# sch.net
KiCad netlist of a schematic drawn in Altium Designer
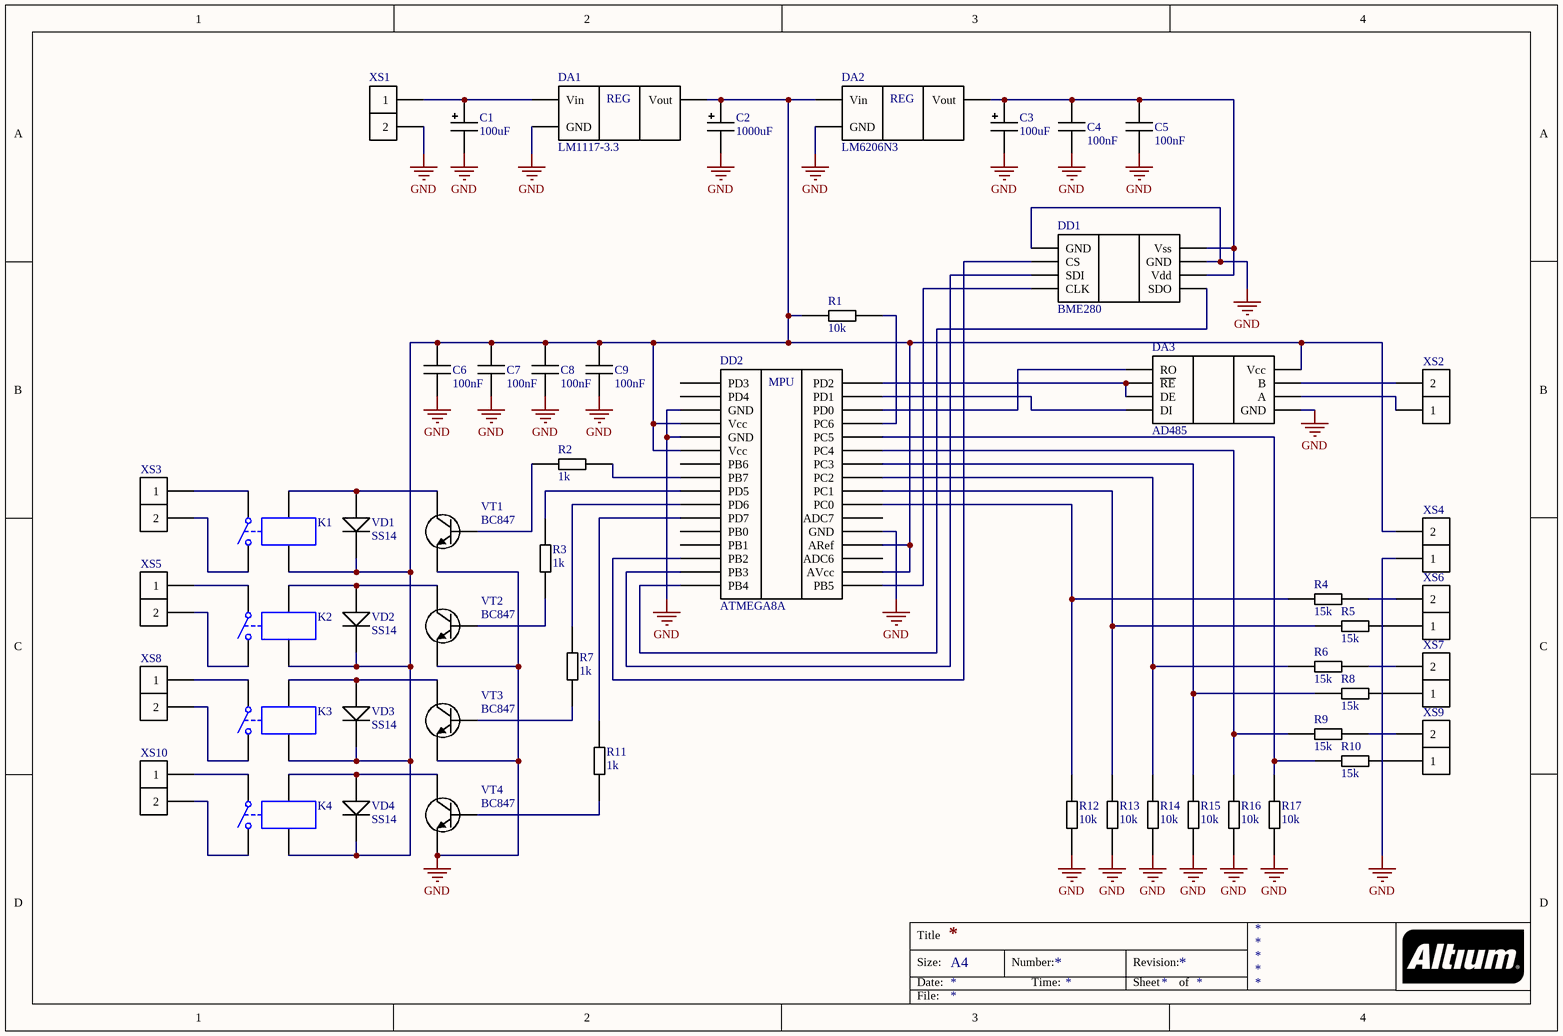
[diagram p0: sch.SchDoc]

(export (version "E")
  (design (tool "Eeschema 10.0.6"))
  (components
    (comp (ref "C1") (value "100uF") (libsource (lib "EDDLib") (part "CAP_POLAR")))
    (comp (ref "C2") (value "1000uF") (libsource (lib "EDDLib") (part "CAP_POLAR")))
    (comp (ref "C3") (value "100uF") (libsource (lib "EDDLib") (part "CAP_POLAR")))
    (comp (ref "C4") (value "100nF") (libsource (lib "EDDLib") (part "CAP_NONPOLAR")))
    (comp (ref "C5") (value "100nF") (libsource (lib "EDDLib") (part "CAP_NONPOLAR")))
    (comp (ref "C6") (value "100nF") (libsource (lib "EDDLib") (part "CAP_NONPOLAR")))
    (comp (ref "C7") (value "100nF") (libsource (lib "EDDLib") (part "CAP_NONPOLAR")))
    (comp (ref "C8") (value "100nF") (libsource (lib "EDDLib") (part "CAP_NONPOLAR")))
    (comp (ref "C9") (value "100nF") (libsource (lib "EDDLib") (part "CAP_NONPOLAR")))
    (comp (ref "DA1") (value "LM1117-3.3") (libsource (lib "EDDLib") (part "LM1117-3.3")))
    (comp (ref "DA2") (value "LM6206N3") (libsource (lib "EDDLib") (part "LM1117-3.3")))
    (comp (ref "DA3") (value "AD485") (libsource (lib "EDDLib") (part "AD485")))
    (comp (ref "DD1") (value "BME280") (libsource (lib "EDDLib") (part "BME280")))
    (comp (ref "DD2") (value "ATMEGA8A") (libsource (lib "EDDLib") (part "ATMEGA8A")))
    (comp (ref "K1")
      (value "Relay-SPST")
      (footprint "MODULE4")
      (description "Single-Pole Single-Throw Relay")
      (fields (field (name "PUBLISHER") "Altium Limited"))
      (libsource (lib "Miscellaneous Devices") (part "Relay-SPST"))
    )
    (comp (ref "K2")
      (value "Relay-SPST")
      (footprint "MODULE4")
      (description "Single-Pole Single-Throw Relay")
      (fields (field (name "PUBLISHER") "Altium Limited"))
      (libsource (lib "Miscellaneous Devices") (part "Relay-SPST"))
    )
    (comp (ref "K3")
      (value "Relay-SPST")
      (footprint "MODULE4")
      (description "Single-Pole Single-Throw Relay")
      (fields (field (name "PUBLISHER") "Altium Limited"))
      (libsource (lib "Miscellaneous Devices") (part "Relay-SPST"))
    )
    (comp (ref "K4")
      (value "Relay-SPST")
      (footprint "MODULE4")
      (description "Single-Pole Single-Throw Relay")
      (fields (field (name "PUBLISHER") "Altium Limited"))
      (libsource (lib "Miscellaneous Devices") (part "Relay-SPST"))
    )
    (comp (ref "R1") (value "10k") (libsource (lib "EDDLib") (part "RES")))
    (comp (ref "R2") (value "1k") (libsource (lib "EDDLib") (part "RES")))
    (comp (ref "R3") (value "1k") (libsource (lib "EDDLib") (part "RES")))
    (comp (ref "R4") (value "15k") (libsource (lib "EDDLib") (part "RES")))
    (comp (ref "R5") (value "15k") (libsource (lib "EDDLib") (part "RES")))
    (comp (ref "R6") (value "15k") (libsource (lib "EDDLib") (part "RES")))
    (comp (ref "R7") (value "1k") (libsource (lib "EDDLib") (part "RES")))
    (comp (ref "R8") (value "15k") (libsource (lib "EDDLib") (part "RES")))
    (comp (ref "R9") (value "15k") (libsource (lib "EDDLib") (part "RES")))
    (comp (ref "R10") (value "15k") (libsource (lib "EDDLib") (part "RES")))
    (comp (ref "R11") (value "1k") (libsource (lib "EDDLib") (part "RES")))
    (comp (ref "R12") (value "10k") (libsource (lib "EDDLib") (part "RES")))
    (comp (ref "R13") (value "10k") (libsource (lib "EDDLib") (part "RES")))
    (comp (ref "R14") (value "10k") (libsource (lib "EDDLib") (part "RES")))
    (comp (ref "R15") (value "10k") (libsource (lib "EDDLib") (part "RES")))
    (comp (ref "R16") (value "10k") (libsource (lib "EDDLib") (part "RES")))
    (comp (ref "R17") (value "10k") (libsource (lib "EDDLib") (part "RES")))
    (comp (ref "VD1")
      (value "SS14")
      (footprint "SMC")
      (description "Default Diode")
      (fields (field (name "PUBLISHER") "Altium Limited"))
      (libsource (lib "EDDLib") (part "Diode"))
    )
    (comp (ref "VD2")
      (value "SS14")
      (footprint "SMC")
      (description "Default Diode")
      (fields (field (name "PUBLISHER") "Altium Limited"))
      (libsource (lib "EDDLib") (part "Diode"))
    )
    (comp (ref "VD3")
      (value "SS14")
      (footprint "SMC")
      (description "Default Diode")
      (fields (field (name "PUBLISHER") "Altium Limited"))
      (libsource (lib "EDDLib") (part "Diode"))
    )
    (comp (ref "VD4")
      (value "SS14")
      (footprint "SMC")
      (description "Default Diode")
      (fields (field (name "PUBLISHER") "Altium Limited"))
      (libsource (lib "EDDLib") (part "Diode"))
    )
    (comp (ref "VT1")
      (value "BC847")
      (footprint "TO-226-AA")
      (description "NPN Bipolar Transistor")
      (fields (field (name "PUBLISHER") "Altium Limited"))
      (libsource (lib "EDDLib") (part "NPN"))
    )
    (comp (ref "VT2")
      (value "BC847")
      (footprint "TO-226-AA")
      (description "NPN Bipolar Transistor")
      (fields (field (name "PUBLISHER") "Altium Limited"))
      (libsource (lib "EDDLib") (part "NPN"))
    )
    (comp (ref "VT3")
      (value "BC847")
      (footprint "TO-226-AA")
      (description "NPN Bipolar Transistor")
      (fields (field (name "PUBLISHER") "Altium Limited"))
      (libsource (lib "EDDLib") (part "NPN"))
    )
    (comp (ref "VT4")
      (value "BC847")
      (footprint "TO-226-AA")
      (description "NPN Bipolar Transistor")
      (fields (field (name "PUBLISHER") "Altium Limited"))
      (libsource (lib "EDDLib") (part "NPN"))
    )
    (comp (ref "XS1") (value "CONN-2") (libsource (lib "EDDLib") (part "CONN-2")))
    (comp (ref "XS2") (value "CONN-2") (libsource (lib "EDDLib") (part "CONN-2")))
    (comp (ref "XS3") (value "CONN-2") (libsource (lib "EDDLib") (part "CONN-2")))
    (comp (ref "XS4") (value "CONN-2") (libsource (lib "EDDLib") (part "CONN-2")))
    (comp (ref "XS5") (value "CONN-2") (libsource (lib "EDDLib") (part "CONN-2")))
    (comp (ref "XS6") (value "CONN-2") (libsource (lib "EDDLib") (part "CONN-2")))
    (comp (ref "XS7") (value "CONN-2") (libsource (lib "EDDLib") (part "CONN-2")))
    (comp (ref "XS8") (value "CONN-2") (libsource (lib "EDDLib") (part "CONN-2")))
    (comp (ref "XS9") (value "CONN-2") (libsource (lib "EDDLib") (part "CONN-2")))
    (comp (ref "XS10") (value "CONN-2") (libsource (lib "EDDLib") (part "CONN-2")))
  )
  (nets
    (net (code "1") (name "GND") (class "Default")
      (node (ref "C1") (pin "2") (pinfunction "2_2") (pintype "passive"))
      (node (ref "C2") (pin "2") (pinfunction "2_2") (pintype "passive"))
      (node (ref "C3") (pin "2") (pinfunction "2_2") (pintype "passive"))
      (node (ref "C4") (pin "2") (pinfunction "2_2") (pintype "passive"))
      (node (ref "C5") (pin "2") (pinfunction "2_2") (pintype "passive"))
      (node (ref "C6") (pin "2") (pinfunction "2_2") (pintype "passive"))
      (node (ref "C7") (pin "2") (pinfunction "2_2") (pintype "passive"))
      (node (ref "C8") (pin "2") (pinfunction "2_2") (pintype "passive"))
      (node (ref "C9") (pin "2") (pinfunction "2_2") (pintype "passive"))
      (node (ref "DA1") (pin "3") (pinfunction "GND_3") (pintype "passive"))
      (node (ref "DA2") (pin "3") (pinfunction "GND_3") (pintype "passive"))
      (node (ref "DA3") (pin "5") (pinfunction "GND_5") (pintype "passive"))
      (node (ref "DD1") (pin "1") (pinfunction "GND_1") (pintype "passive"))
      (node (ref "DD1") (pin "7") (pinfunction "GND_7") (pintype "passive"))
      (node (ref "DD2") (pin "21") (pinfunction "GND_21") (pintype "passive"))
      (node (ref "DD2") (pin "3") (pinfunction "GND_3") (pintype "passive"))
      (node (ref "DD2") (pin "5") (pinfunction "GND_5") (pintype "passive"))
      (node (ref "R12") (pin "2") (pinfunction "2_2") (pintype "passive"))
      (node (ref "R13") (pin "2") (pinfunction "2_2") (pintype "passive"))
      (node (ref "R14") (pin "2") (pinfunction "2_2") (pintype "passive"))
      (node (ref "R15") (pin "2") (pinfunction "2_2") (pintype "passive"))
      (node (ref "R16") (pin "2") (pinfunction "2_2") (pintype "passive"))
      (node (ref "R17") (pin "2") (pinfunction "2_2") (pintype "passive"))
      (node (ref "VT1") (pin "3") (pinfunction "E_3") (pintype "passive"))
      (node (ref "VT2") (pin "3") (pinfunction "E_3") (pintype "passive"))
      (node (ref "VT3") (pin "3") (pinfunction "E_3") (pintype "passive"))
      (node (ref "VT4") (pin "3") (pinfunction "E_3") (pintype "passive"))
      (node (ref "XS1") (pin "2") (pinfunction "2_2") (pintype "passive"))
      (node (ref "XS4") (pin "1") (pinfunction "1_1") (pintype "passive"))
    )
    (net (code "2") (name "Net-(DA1-Vin)") (class "Default")
      (node (ref "C1") (pin "1") (pinfunction "1_1") (pintype "passive"))
      (node (ref "DA1") (pin "1") (pinfunction "Vin_1") (pintype "passive"))
      (node (ref "XS1") (pin "1") (pinfunction "1_1") (pintype "passive"))
    )
    (net (code "3") (name "Net-(DA1-Vout)") (class "Default")
      (node (ref "C2") (pin "1") (pinfunction "1_1") (pintype "passive"))
      (node (ref "C6") (pin "1") (pinfunction "1_1") (pintype "passive"))
      (node (ref "C7") (pin "1") (pinfunction "1_1") (pintype "passive"))
      (node (ref "C8") (pin "1") (pinfunction "1_1") (pintype "passive"))
      (node (ref "C9") (pin "1") (pinfunction "1_1") (pintype "passive"))
      (node (ref "DA1") (pin "2") (pinfunction "Vout_2") (pintype "passive"))
      (node (ref "DA2") (pin "1") (pinfunction "Vin_1") (pintype "passive"))
      (node (ref "DA3") (pin "8") (pinfunction "Vcc_8") (pintype "passive"))
      (node (ref "DD2") (pin "18") (pinfunction "AVcc_18") (pintype "passive"))
      (node (ref "DD2") (pin "20") (pinfunction "ARef_20") (pintype "passive"))
      (node (ref "DD2") (pin "4") (pinfunction "Vcc_4") (pintype "passive"))
      (node (ref "DD2") (pin "6") (pinfunction "Vcc_6") (pintype "passive"))
      (node (ref "K1") (pin "4") (pinfunction "4_4") (pintype "passive"))
      (node (ref "K2") (pin "4") (pinfunction "4_4") (pintype "passive"))
      (node (ref "K3") (pin "4") (pinfunction "4_4") (pintype "passive"))
      (node (ref "K4") (pin "4") (pinfunction "4_4") (pintype "passive"))
      (node (ref "R1") (pin "2") (pinfunction "2_2") (pintype "passive"))
      (node (ref "VD1") (pin "2") (pinfunction "K_2") (pintype "passive"))
      (node (ref "VD2") (pin "2") (pinfunction "K_2") (pintype "passive"))
      (node (ref "VD3") (pin "2") (pinfunction "K_2") (pintype "passive"))
      (node (ref "VD4") (pin "2") (pinfunction "K_2") (pintype "passive"))
      (node (ref "XS4") (pin "2") (pinfunction "2_2") (pintype "passive"))
    )
    (net (code "4") (name "Net-(DA2-Vout)") (class "Default")
      (node (ref "C3") (pin "1") (pinfunction "1_1") (pintype "passive"))
      (node (ref "C4") (pin "1") (pinfunction "1_1") (pintype "passive"))
      (node (ref "C5") (pin "1") (pinfunction "1_1") (pintype "passive"))
      (node (ref "DA2") (pin "2") (pinfunction "Vout_2") (pintype "passive"))
      (node (ref "DD1") (pin "6") (pinfunction "Vdd_6") (pintype "passive"))
      (node (ref "DD1") (pin "8") (pinfunction "Vss_8") (pintype "passive"))
    )
    (net (code "5") (name "Net-(DA3-A)") (class "Default")
      (node (ref "DA3") (pin "6") (pinfunction "A_6") (pintype "passive"))
      (node (ref "XS2") (pin "1") (pinfunction "1_1") (pintype "passive"))
    )
    (net (code "6") (name "Net-(DA3-B)") (class "Default")
      (node (ref "DA3") (pin "7") (pinfunction "B_7") (pintype "passive"))
      (node (ref "XS2") (pin "2") (pinfunction "2_2") (pintype "passive"))
    )
    (net (code "7") (name "Net-(DA3-DE)") (class "Default")
      (node (ref "DA3") (pin "2") (pinfunction "~{RE}_2") (pintype "passive"))
      (node (ref "DA3") (pin "3") (pinfunction "DE_3") (pintype "passive"))
      (node (ref "DD2") (pin "32") (pinfunction "PD2_32") (pintype "passive"))
    )
    (net (code "8") (name "Net-(DA3-DI)") (class "Default")
      (node (ref "DA3") (pin "4") (pinfunction "DI_4") (pintype "passive"))
      (node (ref "DD2") (pin "31") (pinfunction "PD1_31") (pintype "passive"))
    )
    (net (code "9") (name "Net-(DA3-RO)") (class "Default")
      (node (ref "DA3") (pin "1") (pinfunction "RO_1") (pintype "passive"))
      (node (ref "DD2") (pin "30") (pinfunction "PD0_30") (pintype "passive"))
    )
    (net (code "10") (name "Net-(DD1-CLK)") (class "Default")
      (node (ref "DD1") (pin "4") (pinfunction "CLK_4") (pintype "passive"))
      (node (ref "DD2") (pin "17") (pinfunction "PB5_17") (pintype "passive"))
    )
    (net (code "11") (name "Net-(DD1-CS)") (class "Default")
      (node (ref "DD1") (pin "2") (pinfunction "CS_2") (pintype "passive"))
      (node (ref "DD2") (pin "14") (pinfunction "PB2_14") (pintype "passive"))
    )
    (net (code "12") (name "Net-(DD1-SDI)") (class "Default")
      (node (ref "DD1") (pin "3") (pinfunction "SDI_3") (pintype "passive"))
      (node (ref "DD2") (pin "15") (pinfunction "PB3_15") (pintype "passive"))
    )
    (net (code "13") (name "Net-(DD1-SDO)") (class "Default")
      (node (ref "DD1") (pin "5") (pinfunction "SDO_5") (pintype "passive"))
      (node (ref "DD2") (pin "16") (pinfunction "PB4_16") (pintype "passive"))
    )
    (net (code "14") (name "Net-(DD2-PB7)") (class "Default")
      (node (ref "DD2") (pin "8") (pinfunction "PB7_8") (pintype "passive"))
      (node (ref "R2") (pin "1") (pinfunction "1_1") (pintype "passive"))
    )
    (net (code "15") (name "Net-(DD2-PC0)") (class "Default")
      (node (ref "DD2") (pin "23") (pinfunction "PC0_23") (pintype "passive"))
      (node (ref "R12") (pin "1") (pinfunction "1_1") (pintype "passive"))
      (node (ref "R4") (pin "1") (pinfunction "1_1") (pintype "passive"))
    )
    (net (code "16") (name "Net-(DD2-PC1)") (class "Default")
      (node (ref "DD2") (pin "24") (pinfunction "PC1_24") (pintype "passive"))
      (node (ref "R13") (pin "1") (pinfunction "1_1") (pintype "passive"))
      (node (ref "R5") (pin "1") (pinfunction "1_1") (pintype "passive"))
    )
    (net (code "17") (name "Net-(DD2-PC2)") (class "Default")
      (node (ref "DD2") (pin "25") (pinfunction "PC2_25") (pintype "passive"))
      (node (ref "R14") (pin "1") (pinfunction "1_1") (pintype "passive"))
      (node (ref "R6") (pin "1") (pinfunction "1_1") (pintype "passive"))
    )
    (net (code "18") (name "Net-(DD2-PC3)") (class "Default")
      (node (ref "DD2") (pin "26") (pinfunction "PC3_26") (pintype "passive"))
      (node (ref "R15") (pin "1") (pinfunction "1_1") (pintype "passive"))
      (node (ref "R8") (pin "1") (pinfunction "1_1") (pintype "passive"))
    )
    (net (code "19") (name "Net-(DD2-PC4)") (class "Default")
      (node (ref "DD2") (pin "27") (pinfunction "PC4_27") (pintype "passive"))
      (node (ref "R16") (pin "1") (pinfunction "1_1") (pintype "passive"))
      (node (ref "R9") (pin "1") (pinfunction "1_1") (pintype "passive"))
    )
    (net (code "20") (name "Net-(DD2-PC5)") (class "Default")
      (node (ref "DD2") (pin "28") (pinfunction "PC5_28") (pintype "passive"))
      (node (ref "R10") (pin "1") (pinfunction "1_1") (pintype "passive"))
      (node (ref "R17") (pin "1") (pinfunction "1_1") (pintype "passive"))
    )
    (net (code "21") (name "Net-(DD2-PC6)") (class "Default")
      (node (ref "DD2") (pin "29") (pinfunction "PC6_29") (pintype "passive"))
      (node (ref "R1") (pin "1") (pinfunction "1_1") (pintype "passive"))
    )
    (net (code "22") (name "Net-(DD2-PD5)") (class "Default")
      (node (ref "DD2") (pin "9") (pinfunction "PD5_9") (pintype "passive"))
      (node (ref "R3") (pin "1") (pinfunction "1_1") (pintype "passive"))
    )
    (net (code "23") (name "Net-(DD2-PD6)") (class "Default")
      (node (ref "DD2") (pin "10") (pinfunction "PD6_10") (pintype "passive"))
      (node (ref "R7") (pin "1") (pinfunction "1_1") (pintype "passive"))
    )
    (net (code "24") (name "Net-(DD2-PD7)") (class "Default")
      (node (ref "DD2") (pin "11") (pinfunction "PD7_11") (pintype "passive"))
      (node (ref "R11") (pin "1") (pinfunction "1_1") (pintype "passive"))
    )
    (net (code "25") (name "Net-(K1-Pad1)") (class "Default")
      (node (ref "K1") (pin "1") (pinfunction "1_1") (pintype "passive"))
      (node (ref "XS3") (pin "1") (pinfunction "1_1") (pintype "passive"))
    )
    (net (code "26") (name "Net-(K1-Pad2)") (class "Default")
      (node (ref "K1") (pin "2") (pinfunction "2_2") (pintype "passive"))
      (node (ref "XS3") (pin "2") (pinfunction "2_2") (pintype "passive"))
    )
    (net (code "27") (name "Net-(K2-Pad1)") (class "Default")
      (node (ref "K2") (pin "1") (pinfunction "1_1") (pintype "passive"))
      (node (ref "XS5") (pin "1") (pinfunction "1_1") (pintype "passive"))
    )
    (net (code "28") (name "Net-(K2-Pad2)") (class "Default")
      (node (ref "K2") (pin "2") (pinfunction "2_2") (pintype "passive"))
      (node (ref "XS5") (pin "2") (pinfunction "2_2") (pintype "passive"))
    )
    (net (code "29") (name "Net-(K3-Pad1)") (class "Default")
      (node (ref "K3") (pin "1") (pinfunction "1_1") (pintype "passive"))
      (node (ref "XS8") (pin "1") (pinfunction "1_1") (pintype "passive"))
    )
    (net (code "30") (name "Net-(K3-Pad2)") (class "Default")
      (node (ref "K3") (pin "2") (pinfunction "2_2") (pintype "passive"))
      (node (ref "XS8") (pin "2") (pinfunction "2_2") (pintype "passive"))
    )
    (net (code "31") (name "Net-(K4-Pad1)") (class "Default")
      (node (ref "K4") (pin "1") (pinfunction "1_1") (pintype "passive"))
      (node (ref "XS10") (pin "1") (pinfunction "1_1") (pintype "passive"))
    )
    (net (code "32") (name "Net-(K4-Pad2)") (class "Default")
      (node (ref "K4") (pin "2") (pinfunction "2_2") (pintype "passive"))
      (node (ref "XS10") (pin "2") (pinfunction "2_2") (pintype "passive"))
    )
    (net (code "33") (name "Net-(R4-Pad2)") (class "Default")
      (node (ref "R4") (pin "2") (pinfunction "2_2") (pintype "passive"))
      (node (ref "XS6") (pin "2") (pinfunction "2_2") (pintype "passive"))
    )
    (net (code "34") (name "Net-(R5-Pad2)") (class "Default")
      (node (ref "R5") (pin "2") (pinfunction "2_2") (pintype "passive"))
      (node (ref "XS6") (pin "1") (pinfunction "1_1") (pintype "passive"))
    )
    (net (code "35") (name "Net-(R6-Pad2)") (class "Default")
      (node (ref "R6") (pin "2") (pinfunction "2_2") (pintype "passive"))
      (node (ref "XS7") (pin "2") (pinfunction "2_2") (pintype "passive"))
    )
    (net (code "36") (name "Net-(R8-Pad2)") (class "Default")
      (node (ref "R8") (pin "2") (pinfunction "2_2") (pintype "passive"))
      (node (ref "XS7") (pin "1") (pinfunction "1_1") (pintype "passive"))
    )
    (net (code "37") (name "Net-(R9-Pad2)") (class "Default")
      (node (ref "R9") (pin "2") (pinfunction "2_2") (pintype "passive"))
      (node (ref "XS9") (pin "2") (pinfunction "2_2") (pintype "passive"))
    )
    (net (code "38") (name "Net-(R10-Pad2)") (class "Default")
      (node (ref "R10") (pin "2") (pinfunction "2_2") (pintype "passive"))
      (node (ref "XS9") (pin "1") (pinfunction "1_1") (pintype "passive"))
    )
    (net (code "39") (name "Net-(VD1-A)") (class "Default")
      (node (ref "K1") (pin "3") (pinfunction "3_3") (pintype "passive"))
      (node (ref "VD1") (pin "1") (pinfunction "A_1") (pintype "passive"))
      (node (ref "VT1") (pin "1") (pinfunction "C_1") (pintype "passive"))
    )
    (net (code "40") (name "Net-(VD2-A)") (class "Default")
      (node (ref "K2") (pin "3") (pinfunction "3_3") (pintype "passive"))
      (node (ref "VD2") (pin "1") (pinfunction "A_1") (pintype "passive"))
      (node (ref "VT2") (pin "1") (pinfunction "C_1") (pintype "passive"))
    )
    (net (code "41") (name "Net-(VD3-A)") (class "Default")
      (node (ref "K3") (pin "3") (pinfunction "3_3") (pintype "passive"))
      (node (ref "VD3") (pin "1") (pinfunction "A_1") (pintype "passive"))
      (node (ref "VT3") (pin "1") (pinfunction "C_1") (pintype "passive"))
    )
    (net (code "42") (name "Net-(VD4-A)") (class "Default")
      (node (ref "K4") (pin "3") (pinfunction "3_3") (pintype "passive"))
      (node (ref "VD4") (pin "1") (pinfunction "A_1") (pintype "passive"))
      (node (ref "VT4") (pin "1") (pinfunction "C_1") (pintype "passive"))
    )
    (net (code "43") (name "Net-(VT1-B)") (class "Default")
      (node (ref "R2") (pin "2") (pinfunction "2_2") (pintype "passive"))
      (node (ref "VT1") (pin "2") (pinfunction "B_2") (pintype "passive"))
    )
    (net (code "44") (name "Net-(VT2-B)") (class "Default")
      (node (ref "R3") (pin "2") (pinfunction "2_2") (pintype "passive"))
      (node (ref "VT2") (pin "2") (pinfunction "B_2") (pintype "passive"))
    )
    (net (code "45") (name "Net-(VT3-B)") (class "Default")
      (node (ref "R7") (pin "2") (pinfunction "2_2") (pintype "passive"))
      (node (ref "VT3") (pin "2") (pinfunction "B_2") (pintype "passive"))
    )
    (net (code "46") (name "Net-(VT4-B)") (class "Default")
      (node (ref "R11") (pin "2") (pinfunction "2_2") (pintype "passive"))
      (node (ref "VT4") (pin "2") (pinfunction "B_2") (pintype "passive"))
    )
    (net (code "47") (name "unconnected-(DD2-ADC6-Pad19)") (class "Default")
      (node (ref "DD2") (pin "19") (pinfunction "ADC6_19") (pintype "passive"))
    )
    (net (code "48") (name "unconnected-(DD2-ADC7-Pad22)") (class "Default")
      (node (ref "DD2") (pin "22") (pinfunction "ADC7_22") (pintype "passive"))
    )
    (net (code "49") (name "unconnected-(DD2-PB0-Pad12)") (class "Default")
      (node (ref "DD2") (pin "12") (pinfunction "PB0_12") (pintype "passive"))
    )
    (net (code "50") (name "unconnected-(DD2-PB1-Pad13)") (class "Default")
      (node (ref "DD2") (pin "13") (pinfunction "PB1_13") (pintype "passive"))
    )
    (net (code "51") (name "unconnected-(DD2-PB6-Pad7)") (class "Default")
      (node (ref "DD2") (pin "7") (pinfunction "PB6_7") (pintype "passive"))
    )
    (net (code "52") (name "unconnected-(DD2-PD3-Pad1)") (class "Default")
      (node (ref "DD2") (pin "1") (pinfunction "PD3_1") (pintype "passive"))
    )
    (net (code "53") (name "unconnected-(DD2-PD4-Pad2)") (class "Default")
      (node (ref "DD2") (pin "2") (pinfunction "PD4_2") (pintype "passive"))
    )
  )
)
